# level.net
KiCad netlist of a schematic drawn in EAGLE
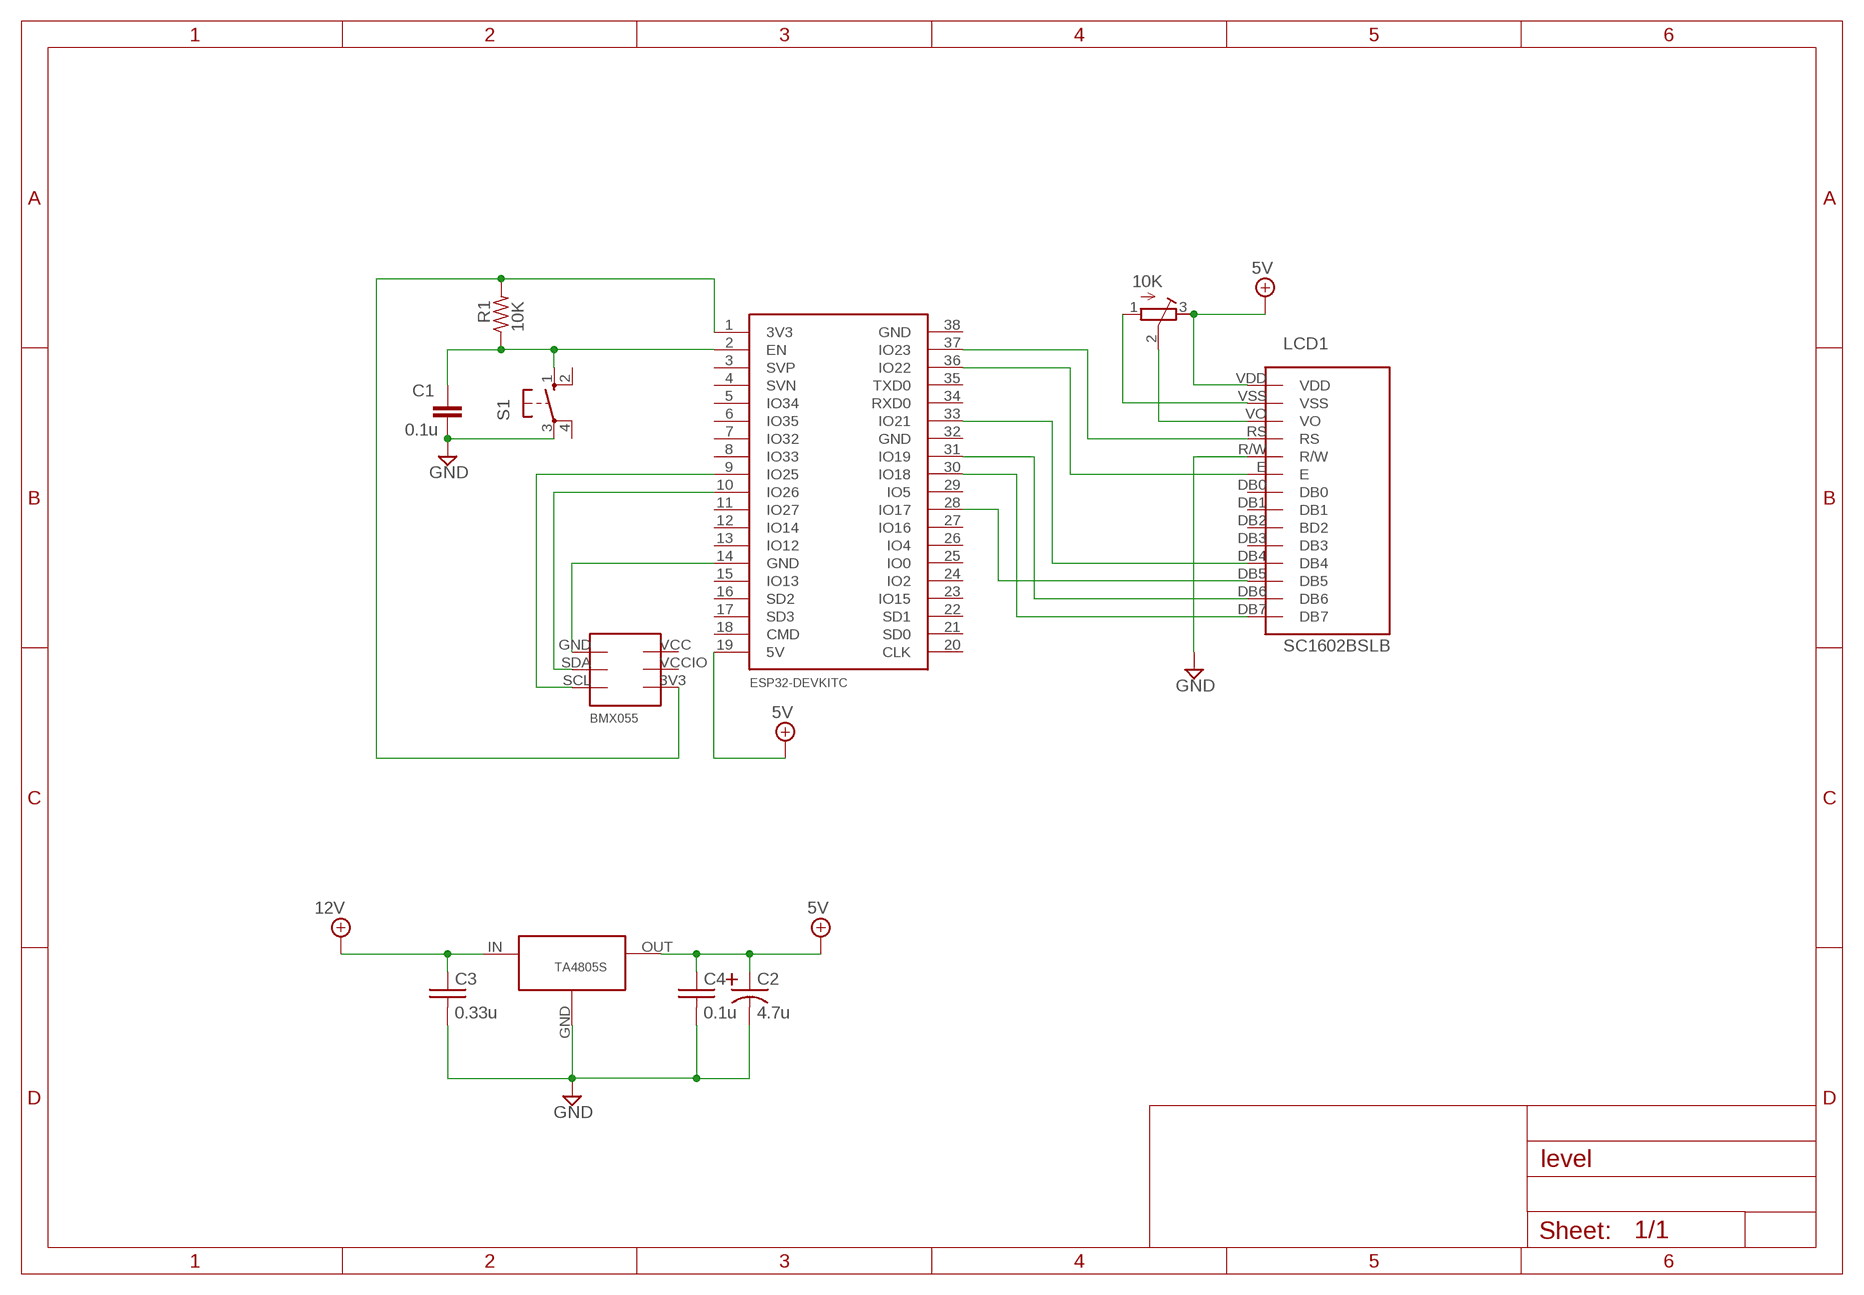
[diagram p0: schematic, sheet 1]

(export (version "E")
  (design (tool "Eeschema 10.0.6"))
  (components
    (comp (ref "C1")
      (value "0.1u")
      (footprint "eagle-import:XC10B5")
      (libsource (lib "eagle-import") (part "CAPACITOR"))
    )
    (comp (ref "C2")
      (value "4.7u")
      (footprint "eagle-import:ELECTROLYTIC-LAYDWN")
      (libsource (lib "eagle-import") (part "ELECTROLYTICLAYDWN"))
    )
    (comp (ref "C3")
      (value "0.33u")
      (footprint "eagle-import:XC10B5")
      (libsource (lib "eagle-import") (part "Capacitor_CAPACITOR"))
    )
    (comp (ref "C4")
      (value "0.1u")
      (footprint "eagle-import:XC10B5")
      (libsource (lib "eagle-import") (part "Capacitor_CAPACITOR"))
    )
    (comp (ref "LCD1")
      (value "SC1602BSLB")
      (footprint "eagle-import:SC1602BSLB")
      (libsource (lib "eagle-import") (part "SC1602BSLB"))
    )
    (comp (ref "R1")
      (value "10K")
      (footprint "eagle-import:0204_7")
      (libsource (lib "eagle-import") (part "R-US_0204/7"))
    )
    (comp (ref "S1")
      (value "SWITCH")
      (footprint "eagle-import:B3F-10XX")
      (fields (field (name "MPN") "B3F-1000"))
      (libsource (lib "eagle-import") (part "SWITCH"))
    )
    (comp (ref "TA4805S")
      (value "REGULATOR")
      (footprint "eagle-import:REGULATOR")
      (libsource (lib "eagle-import") (part "REGULATOR"))
    )
    (comp (ref "U$1")
      (value "ESP32DEVKITC")
      (footprint "eagle-import:ESP32-DEVKITC")
      (libsource (lib "eagle-import") (part "ESP32DEVKITC"))
    )
    (comp (ref "U$3")
      (value "BMX055")
      (footprint "eagle-import:BMX055")
      (libsource (lib "eagle-import") (part "BMX055"))
    )
    (comp (ref "VR1")
      (value "10K")
      (footprint "eagle-import:VR")
      (libsource (lib "eagle-import") (part "VR"))
    )
  )
  (nets
    (net (code "1") (name "5V") (class "Default")
      (node (ref "C2") (pin "P") (pinfunction "P_P") (pintype "passive"))
      (node (ref "C4") (pin "2") (pinfunction "P_2") (pintype "passive"))
      (node (ref "LCD1") (pin "VDD") (pinfunction "VDD_VDD") (pintype "bidirectional"))
      (node (ref "TA4805S") (pin "OUT") (pinfunction "OUT_OUT") (pintype "bidirectional"))
      (node (ref "U$1") (pin "19") (pinfunction "5V_19") (pintype "bidirectional"))
      (node (ref "VR1") (pin "3") (pinfunction "E_3") (pintype "passive"))
    )
    (net (code "2") (name "12V") (class "Default")
      (node (ref "C3") (pin "2") (pinfunction "P_2") (pintype "passive"))
      (node (ref "TA4805S") (pin "IN") (pinfunction "IN_IN") (pintype "bidirectional"))
    )
    (net (code "3") (name "GND") (class "Default")
      (node (ref "C1") (pin "2") (pinfunction "2_2") (pintype "passive"))
      (node (ref "C2") (pin "N") (pinfunction "N_N") (pintype "passive"))
      (node (ref "C3") (pin "1") (pinfunction "N_1") (pintype "passive"))
      (node (ref "C4") (pin "1") (pinfunction "N_1") (pintype "passive"))
      (node (ref "LCD1") (pin "R/W") (pinfunction "R/W_R/W") (pintype "bidirectional"))
      (node (ref "S1") (pin "3") (pinfunction "P_3") (pintype "passive"))
      (node (ref "TA4805S") (pin "GND") (pinfunction "GND_GND") (pintype "bidirectional"))
    )
    (net (code "4") (name "Net-(S1-S)") (class "Default")
      (node (ref "C1") (pin "1") (pinfunction "1_1") (pintype "passive"))
      (node (ref "R1") (pin "1") (pinfunction "1_1") (pintype "passive"))
      (node (ref "S1") (pin "1") (pinfunction "S_1") (pintype "passive"))
      (node (ref "U$1") (pin "2") (pinfunction "EN_2") (pintype "bidirectional"))
    )
    (net (code "5") (name "Net-(U$1-3V3)") (class "Default")
      (node (ref "R1") (pin "2") (pinfunction "2_2") (pintype "passive"))
      (node (ref "U$1") (pin "1") (pinfunction "3V3_1") (pintype "bidirectional"))
      (node (ref "U$3") (pin "3V3") (pinfunction "3V3_3V3") (pintype "bidirectional"))
    )
    (net (code "6") (name "Net-(U$1-GND-Pad14)") (class "Default")
      (node (ref "U$1") (pin "14") (pinfunction "GND_14") (pintype "bidirectional"))
      (node (ref "U$3") (pin "GND") (pinfunction "GND_GND") (pintype "bidirectional"))
    )
    (net (code "7") (name "Net-(U$1-IO17)") (class "Default")
      (node (ref "LCD1") (pin "DB5") (pinfunction "DB5_DB5") (pintype "bidirectional"))
      (node (ref "U$1") (pin "28") (pinfunction "IO17_28") (pintype "bidirectional"))
    )
    (net (code "8") (name "Net-(U$1-IO18)") (class "Default")
      (node (ref "LCD1") (pin "DB7") (pinfunction "DB7_DB7") (pintype "bidirectional"))
      (node (ref "U$1") (pin "30") (pinfunction "IO18_30") (pintype "bidirectional"))
    )
    (net (code "9") (name "Net-(U$1-IO19)") (class "Default")
      (node (ref "LCD1") (pin "DB6") (pinfunction "DB6_DB6") (pintype "bidirectional"))
      (node (ref "U$1") (pin "31") (pinfunction "IO19_31") (pintype "bidirectional"))
    )
    (net (code "10") (name "Net-(U$1-IO21)") (class "Default")
      (node (ref "LCD1") (pin "DB4") (pinfunction "DB4_DB4") (pintype "bidirectional"))
      (node (ref "U$1") (pin "33") (pinfunction "IO21_33") (pintype "bidirectional"))
    )
    (net (code "11") (name "Net-(U$1-IO22)") (class "Default")
      (node (ref "LCD1") (pin "E") (pinfunction "E_E") (pintype "bidirectional"))
      (node (ref "U$1") (pin "36") (pinfunction "IO22_36") (pintype "bidirectional"))
    )
    (net (code "12") (name "Net-(U$1-IO23)") (class "Default")
      (node (ref "LCD1") (pin "RS") (pinfunction "RS_RS") (pintype "bidirectional"))
      (node (ref "U$1") (pin "37") (pinfunction "IO23_37") (pintype "bidirectional"))
    )
    (net (code "13") (name "Net-(U$1-IO25)") (class "Default")
      (node (ref "U$1") (pin "9") (pinfunction "IO25_9") (pintype "bidirectional"))
      (node (ref "U$3") (pin "SCL") (pinfunction "SCL_SCL") (pintype "bidirectional"))
    )
    (net (code "14") (name "Net-(U$1-IO26)") (class "Default")
      (node (ref "U$1") (pin "10") (pinfunction "IO26_10") (pintype "bidirectional"))
      (node (ref "U$3") (pin "SDA") (pinfunction "SDA_SDA") (pintype "bidirectional"))
    )
    (net (code "15") (name "Net-(VR1-A)") (class "Default")
      (node (ref "LCD1") (pin "VSS") (pinfunction "VSS_VSS") (pintype "bidirectional"))
      (node (ref "VR1") (pin "1") (pinfunction "A_1") (pintype "passive"))
    )
    (net (code "16") (name "Net-(VR1-S)") (class "Default")
      (node (ref "LCD1") (pin "VO") (pinfunction "VO_VO") (pintype "bidirectional"))
      (node (ref "VR1") (pin "2") (pinfunction "S_2") (pintype "passive"))
    )
    (net (code "17") (name "unconnected-(LCD1-BD2-PadDB2)") (class "Default")
      (node (ref "LCD1") (pin "DB2") (pinfunction "BD2_DB2") (pintype "bidirectional"))
    )
    (net (code "18") (name "unconnected-(LCD1-PadDB0)") (class "Default")
      (node (ref "LCD1") (pin "DB0") (pinfunction "DB0_DB0") (pintype "bidirectional"))
    )
    (net (code "19") (name "unconnected-(LCD1-PadDB1)") (class "Default")
      (node (ref "LCD1") (pin "DB1") (pinfunction "DB1_DB1") (pintype "bidirectional"))
    )
    (net (code "20") (name "unconnected-(LCD1-PadDB3)") (class "Default")
      (node (ref "LCD1") (pin "DB3") (pinfunction "DB3_DB3") (pintype "bidirectional"))
    )
    (net (code "21") (name "unconnected-(S1-P1-Pad4)") (class "Default")
      (node (ref "S1") (pin "4") (pinfunction "P1_4") (pintype "passive"))
    )
    (net (code "22") (name "unconnected-(S1-S1-Pad2)") (class "Default")
      (node (ref "S1") (pin "2") (pinfunction "S1_2") (pintype "passive"))
    )
    (net (code "23") (name "unconnected-(U$1-CLK-Pad20)") (class "Default")
      (node (ref "U$1") (pin "20") (pinfunction "CLK_20") (pintype "bidirectional"))
    )
    (net (code "24") (name "unconnected-(U$1-CMD-Pad18)") (class "Default")
      (node (ref "U$1") (pin "18") (pinfunction "CMD_18") (pintype "bidirectional"))
    )
    (net (code "25") (name "unconnected-(U$1-GND-Pad32)") (class "Default")
      (node (ref "U$1") (pin "32") (pinfunction "GND_32") (pintype "bidirectional"))
    )
    (net (code "26") (name "unconnected-(U$1-GND-Pad38)") (class "Default")
      (node (ref "U$1") (pin "38") (pinfunction "GND_38") (pintype "bidirectional"))
    )
    (net (code "27") (name "unconnected-(U$1-IO0-Pad25)") (class "Default")
      (node (ref "U$1") (pin "25") (pinfunction "IO0_25") (pintype "bidirectional"))
    )
    (net (code "28") (name "unconnected-(U$1-IO2-Pad24)") (class "Default")
      (node (ref "U$1") (pin "24") (pinfunction "IO2_24") (pintype "bidirectional"))
    )
    (net (code "29") (name "unconnected-(U$1-IO4-Pad26)") (class "Default")
      (node (ref "U$1") (pin "26") (pinfunction "IO4_26") (pintype "bidirectional"))
    )
    (net (code "30") (name "unconnected-(U$1-IO5-Pad29)") (class "Default")
      (node (ref "U$1") (pin "29") (pinfunction "IO5_29") (pintype "bidirectional"))
    )
    (net (code "31") (name "unconnected-(U$1-IO12-Pad13)") (class "Default")
      (node (ref "U$1") (pin "13") (pinfunction "IO12_13") (pintype "bidirectional"))
    )
    (net (code "32") (name "unconnected-(U$1-IO13-Pad15)") (class "Default")
      (node (ref "U$1") (pin "15") (pinfunction "IO13_15") (pintype "bidirectional"))
    )
    (net (code "33") (name "unconnected-(U$1-IO14-Pad12)") (class "Default")
      (node (ref "U$1") (pin "12") (pinfunction "IO14_12") (pintype "bidirectional"))
    )
    (net (code "34") (name "unconnected-(U$1-IO15-Pad23)") (class "Default")
      (node (ref "U$1") (pin "23") (pinfunction "IO15_23") (pintype "bidirectional"))
    )
    (net (code "35") (name "unconnected-(U$1-IO16-Pad27)") (class "Default")
      (node (ref "U$1") (pin "27") (pinfunction "IO16_27") (pintype "bidirectional"))
    )
    (net (code "36") (name "unconnected-(U$1-IO27-Pad11)") (class "Default")
      (node (ref "U$1") (pin "11") (pinfunction "IO27_11") (pintype "bidirectional"))
    )
    (net (code "37") (name "unconnected-(U$1-IO32-Pad7)") (class "Default")
      (node (ref "U$1") (pin "7") (pinfunction "IO32_7") (pintype "bidirectional"))
    )
    (net (code "38") (name "unconnected-(U$1-IO33-Pad8)") (class "Default")
      (node (ref "U$1") (pin "8") (pinfunction "IO33_8") (pintype "bidirectional"))
    )
    (net (code "39") (name "unconnected-(U$1-IO34-Pad5)") (class "Default")
      (node (ref "U$1") (pin "5") (pinfunction "IO34_5") (pintype "bidirectional"))
    )
    (net (code "40") (name "unconnected-(U$1-IO35-Pad6)") (class "Default")
      (node (ref "U$1") (pin "6") (pinfunction "IO35_6") (pintype "bidirectional"))
    )
    (net (code "41") (name "unconnected-(U$1-RXD0-Pad34)") (class "Default")
      (node (ref "U$1") (pin "34") (pinfunction "RXD0_34") (pintype "bidirectional"))
    )
    (net (code "42") (name "unconnected-(U$1-SD0-Pad21)") (class "Default")
      (node (ref "U$1") (pin "21") (pinfunction "SD0_21") (pintype "bidirectional"))
    )
    (net (code "43") (name "unconnected-(U$1-SD1-Pad22)") (class "Default")
      (node (ref "U$1") (pin "22") (pinfunction "SD1_22") (pintype "bidirectional"))
    )
    (net (code "44") (name "unconnected-(U$1-SD2-Pad16)") (class "Default")
      (node (ref "U$1") (pin "16") (pinfunction "SD2_16") (pintype "bidirectional"))
    )
    (net (code "45") (name "unconnected-(U$1-SD3-Pad17)") (class "Default")
      (node (ref "U$1") (pin "17") (pinfunction "SD3_17") (pintype "bidirectional"))
    )
    (net (code "46") (name "unconnected-(U$1-SVN-Pad4)") (class "Default")
      (node (ref "U$1") (pin "4") (pinfunction "SVN_4") (pintype "bidirectional"))
    )
    (net (code "47") (name "unconnected-(U$1-SVP-Pad3)") (class "Default")
      (node (ref "U$1") (pin "3") (pinfunction "SVP_3") (pintype "bidirectional"))
    )
    (net (code "48") (name "unconnected-(U$1-TXD0-Pad35)") (class "Default")
      (node (ref "U$1") (pin "35") (pinfunction "TXD0_35") (pintype "bidirectional"))
    )
    (net (code "49") (name "unconnected-(U$3-PadVCC)") (class "Default")
      (node (ref "U$3") (pin "VCC") (pinfunction "VCC_VCC") (pintype "bidirectional"))
    )
    (net (code "50") (name "unconnected-(U$3-PadVCCIO)") (class "Default")
      (node (ref "U$3") (pin "VCCIO") (pinfunction "VCCIO_VCCIO") (pintype "bidirectional"))
    )
  )
)
